# GBxCart_RW_v1_0_Schematic.net
KiCad netlist of a schematic drawn in EAGLE
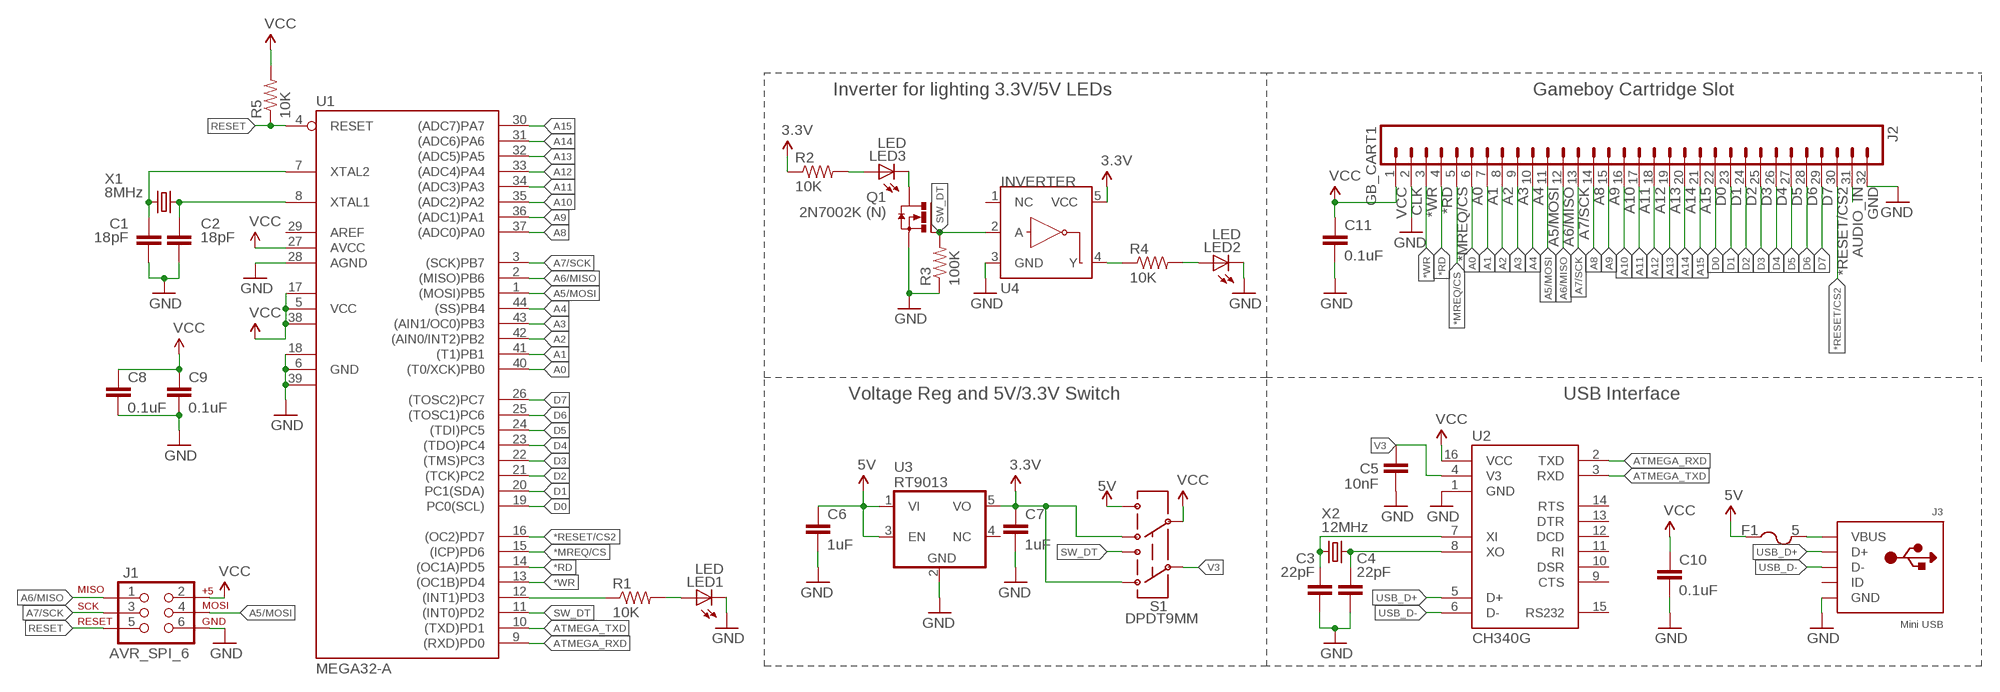
[diagram p0: schematic, sheet 1]

(export (version "E")
  (design (tool "Eeschema 10.0.6"))
  (components
    (comp (ref "C1")
      (value "18pF")
      (footprint "eagle-import:C0805K")
      (libsource (lib "eagle-import") (part "CAP0805"))
    )
    (comp (ref "C2")
      (value "18pF")
      (footprint "eagle-import:C0805K")
      (libsource (lib "eagle-import") (part "CAP0805"))
    )
    (comp (ref "C3")
      (value "22pF")
      (footprint "eagle-import:C0805K")
      (libsource (lib "eagle-import") (part "CAP0805"))
    )
    (comp (ref "C4")
      (value "22pF")
      (footprint "eagle-import:C0805K")
      (libsource (lib "eagle-import") (part "CAP0805"))
    )
    (comp (ref "C5")
      (value "10nF")
      (footprint "eagle-import:C0805K")
      (libsource (lib "eagle-import") (part "CAP0805"))
    )
    (comp (ref "C6")
      (value "1uF")
      (footprint "eagle-import:C0805K")
      (libsource (lib "eagle-import") (part "CAP0805"))
    )
    (comp (ref "C7")
      (value "1uF")
      (footprint "eagle-import:C0805K")
      (libsource (lib "eagle-import") (part "CAP0805"))
    )
    (comp (ref "C8")
      (value "0.1uF")
      (footprint "eagle-import:C0805K")
      (libsource (lib "eagle-import") (part "CAP0805"))
    )
    (comp (ref "C9")
      (value "0.1uF")
      (footprint "eagle-import:C0805K")
      (libsource (lib "eagle-import") (part "CAP0805"))
    )
    (comp (ref "C10")
      (value "0.1uF")
      (footprint "eagle-import:C0805K")
      (libsource (lib "eagle-import") (part "CAP0805"))
    )
    (comp (ref "C11")
      (value "0.1uF")
      (footprint "eagle-import:C0805K")
      (libsource (lib "eagle-import") (part "CAP0805"))
    )
    (comp (ref "F1")
      (value "5")
      (footprint "eagle-import:R1206")
      (libsource (lib "eagle-import") (part "PTCFUSE-1206"))
    )
    (comp (ref "J1")
      (value "AVR_SPI_6")
      (footprint "eagle-import:2X3_2")
      (libsource (lib "eagle-import") (part "AVR_SPI_PRG_6"))
    )
    (comp (ref "J2")
      (value "GB_CART1")
      (footprint "eagle-import:GB_CART_1")
      (libsource (lib "eagle-import") (part "GB_CART1"))
    )
    (comp (ref "J3")
      (value "Mini USB")
      (footprint "eagle-import:USB-MINIB")
      (libsource (lib "eagle-import") (part "USBMINIB"))
    )
    (comp (ref "LED1")
      (value "LED")
      (footprint "eagle-import:CHIP-LED0805")
      (libsource (lib "eagle-import") (part "LEDCHIP-LED0805"))
    )
    (comp (ref "LED2")
      (value "LED")
      (footprint "eagle-import:CHIP-LED0805")
      (libsource (lib "eagle-import") (part "LEDCHIP-LED0805"))
    )
    (comp (ref "LED3")
      (value "LED")
      (footprint "eagle-import:CHIP-LED0805")
      (libsource (lib "eagle-import") (part "LEDCHIP-LED0805"))
    )
    (comp (ref "Q1")
      (value "2N7002K (N)")
      (footprint "eagle-import:SOT-23")
      (libsource (lib "eagle-import") (part "2N7002K_(N)SOT-23"))
    )
    (comp (ref "R1")
      (value "10K")
      (footprint "eagle-import:R0805_2")
      (libsource (lib "eagle-import") (part "R-US_R0805_2"))
    )
    (comp (ref "R2")
      (value "10K")
      (footprint "eagle-import:R0805_2")
      (libsource (lib "eagle-import") (part "R-US_R0805_2"))
    )
    (comp (ref "R3")
      (value "100K")
      (footprint "eagle-import:R0805_2")
      (libsource (lib "eagle-import") (part "R-US_R0805_2"))
    )
    (comp (ref "R4")
      (value "10K")
      (footprint "eagle-import:R0805_2")
      (libsource (lib "eagle-import") (part "R-US_R0805_2"))
    )
    (comp (ref "R5")
      (value "10K")
      (footprint "eagle-import:R0805_2")
      (libsource (lib "eagle-import") (part "R-US_R0805_2"))
    )
    (comp (ref "S1")
      (value "DPDT9MM")
      (footprint "eagle-import:DPDT-3")
      (libsource (lib "eagle-import") (part "SWITCH-DPDT9MM-DIP"))
    )
    (comp (ref "U1")
      (value "MEGA32-A")
      (footprint "eagle-import:TQFP44")
      (libsource (lib "eagle-import") (part "MEGA32-A"))
    )
    (comp (ref "U2")
      (value "CH340G")
      (footprint "eagle-import:SO16")
      (libsource (lib "eagle-import") (part "CH340G"))
    )
    (comp (ref "U3")
      (value "RT9013")
      (footprint "eagle-import:SOT23-5L")
      (libsource (lib "eagle-import") (part "RT9013"))
    )
    (comp (ref "U4")
      (value "INVERTER")
      (footprint "eagle-import:SOT23-5")
      (libsource (lib "eagle-import") (part "INVERTER"))
    )
    (comp (ref "X1")
      (value "8MHz")
      (footprint "eagle-import:HC49U-V")
      (libsource (lib "eagle-import") (part "CRYSTALHC49U-V"))
    )
    (comp (ref "X2")
      (value "12MHz")
      (footprint "eagle-import:HC49U-V")
      (libsource (lib "eagle-import") (part "CRYSTALHC49U-V"))
    )
  )
  (nets
    (net (code "1") (name "*MREQ{slash}CS") (class "Default")
      (node (ref "J2") (pin "5") (pinfunction "5_5") (pintype "passive"))
      (node (ref "U1") (pin "15") (pinfunction "(ICP)PD6_15") (pintype "bidirectional"))
    )
    (net (code "2") (name "*RD") (class "Default")
      (node (ref "J2") (pin "4") (pinfunction "4_4") (pintype "passive"))
      (node (ref "U1") (pin "14") (pinfunction "(OC1A)PD5_14") (pintype "bidirectional"))
    )
    (net (code "3") (name "*RESET{slash}CS2") (class "Default")
      (node (ref "J2") (pin "30") (pinfunction "30_30") (pintype "passive"))
      (node (ref "U1") (pin "16") (pinfunction "(OC2)PD7_16") (pintype "bidirectional"))
    )
    (net (code "4") (name "*WR") (class "Default")
      (node (ref "J2") (pin "3") (pinfunction "3_3") (pintype "passive"))
      (node (ref "U1") (pin "13") (pinfunction "(OC1B)PD4_13") (pintype "bidirectional"))
    )
    (net (code "5") (name "/AREF") (class "Default")
      (node (ref "U1") (pin "29") (pinfunction "AREF_29") (pintype "power_in"))
    )
    (net (code "6") (name "/AUDIO_IN") (class "Default")
      (node (ref "J2") (pin "31") (pinfunction "31_31") (pintype "passive"))
    )
    (net (code "7") (name "3.3V") (class "Default")
      (node (ref "C7") (pin "1") (pinfunction "1_1") (pintype "passive"))
      (node (ref "R2") (pin "1") (pinfunction "1_1") (pintype "passive"))
      (node (ref "S1") (pin "1") (pinfunction "1_1") (pintype "bidirectional"))
      (node (ref "S1") (pin "4") (pinfunction "4_4") (pintype "bidirectional"))
      (node (ref "U3") (pin "5") (pinfunction "VO_5") (pintype "passive"))
      (node (ref "U4") (pin "5") (pinfunction "VCC_5") (pintype "bidirectional"))
    )
    (net (code "8") (name "5V") (class "Default")
      (node (ref "C6") (pin "1") (pinfunction "1_1") (pintype "passive"))
      (node (ref "F1") (pin "1") (pinfunction "1_1") (pintype "passive"))
      (node (ref "S1") (pin "6") (pinfunction "6_6") (pintype "bidirectional"))
      (node (ref "U3") (pin "1") (pinfunction "VI_1") (pintype "input"))
      (node (ref "U3") (pin "3") (pinfunction "EN_3") (pintype "input"))
    )
    (net (code "9") (name "A0") (class "Default")
      (node (ref "J2") (pin "6") (pinfunction "6_6") (pintype "passive"))
      (node (ref "U1") (pin "40") (pinfunction "(T0/XCK)PB0_40") (pintype "bidirectional"))
    )
    (net (code "10") (name "A1") (class "Default")
      (node (ref "J2") (pin "7") (pinfunction "7_7") (pintype "passive"))
      (node (ref "U1") (pin "41") (pinfunction "(T1)PB1_41") (pintype "bidirectional"))
    )
    (net (code "11") (name "A2") (class "Default")
      (node (ref "J2") (pin "8") (pinfunction "8_8") (pintype "passive"))
      (node (ref "U1") (pin "42") (pinfunction "(AIN0/INT2)PB2_42") (pintype "bidirectional"))
    )
    (net (code "12") (name "A3") (class "Default")
      (node (ref "J2") (pin "9") (pinfunction "9_9") (pintype "passive"))
      (node (ref "U1") (pin "43") (pinfunction "(AIN1/OC0)PB3_43") (pintype "bidirectional"))
    )
    (net (code "13") (name "A4") (class "Default")
      (node (ref "J2") (pin "10") (pinfunction "10_10") (pintype "passive"))
      (node (ref "U1") (pin "44") (pinfunction "(SS)PB4_44") (pintype "bidirectional"))
    )
    (net (code "14") (name "A5{slash}MOSI") (class "Default")
      (node (ref "J1") (pin "4") (pinfunction "4_4") (pintype "passive"))
      (node (ref "J2") (pin "11") (pinfunction "11_11") (pintype "passive"))
      (node (ref "U1") (pin "1") (pinfunction "(MOSI)PB5_1") (pintype "bidirectional"))
    )
    (net (code "15") (name "A6{slash}MISO") (class "Default")
      (node (ref "J1") (pin "1") (pinfunction "1_1") (pintype "passive"))
      (node (ref "J2") (pin "12") (pinfunction "12_12") (pintype "passive"))
      (node (ref "U1") (pin "2") (pinfunction "(MISO)PB6_2") (pintype "bidirectional"))
    )
    (net (code "16") (name "A7{slash}SCK") (class "Default")
      (node (ref "J1") (pin "3") (pinfunction "3_3") (pintype "passive"))
      (node (ref "J2") (pin "13") (pinfunction "13_13") (pintype "passive"))
      (node (ref "U1") (pin "3") (pinfunction "(SCK)PB7_3") (pintype "bidirectional"))
    )
    (net (code "17") (name "A8") (class "Default")
      (node (ref "J2") (pin "14") (pinfunction "14_14") (pintype "passive"))
      (node (ref "U1") (pin "37") (pinfunction "(ADC0)PA0_37") (pintype "bidirectional"))
    )
    (net (code "18") (name "A9") (class "Default")
      (node (ref "J2") (pin "15") (pinfunction "15_15") (pintype "passive"))
      (node (ref "U1") (pin "36") (pinfunction "(ADC1)PA1_36") (pintype "bidirectional"))
    )
    (net (code "19") (name "A10") (class "Default")
      (node (ref "J2") (pin "16") (pinfunction "16_16") (pintype "passive"))
      (node (ref "U1") (pin "35") (pinfunction "(ADC2)PA2_35") (pintype "bidirectional"))
    )
    (net (code "20") (name "A11") (class "Default")
      (node (ref "J2") (pin "17") (pinfunction "17_17") (pintype "passive"))
      (node (ref "U1") (pin "34") (pinfunction "(ADC3)PA3_34") (pintype "bidirectional"))
    )
    (net (code "21") (name "A12") (class "Default")
      (node (ref "J2") (pin "18") (pinfunction "18_18") (pintype "passive"))
      (node (ref "U1") (pin "33") (pinfunction "(ADC4)PA4_33") (pintype "bidirectional"))
    )
    (net (code "22") (name "A13") (class "Default")
      (node (ref "J2") (pin "19") (pinfunction "19_19") (pintype "passive"))
      (node (ref "U1") (pin "32") (pinfunction "(ADC5)PA5_32") (pintype "bidirectional"))
    )
    (net (code "23") (name "A14") (class "Default")
      (node (ref "J2") (pin "20") (pinfunction "20_20") (pintype "passive"))
      (node (ref "U1") (pin "31") (pinfunction "(ADC6)PA6_31") (pintype "bidirectional"))
    )
    (net (code "24") (name "A15") (class "Default")
      (node (ref "J2") (pin "21") (pinfunction "21_21") (pintype "passive"))
      (node (ref "U1") (pin "30") (pinfunction "(ADC7)PA7_30") (pintype "bidirectional"))
    )
    (net (code "25") (name "ATMEGA_RXD") (class "Default")
      (node (ref "U1") (pin "9") (pinfunction "(RXD)PD0_9") (pintype "bidirectional"))
      (node (ref "U2") (pin "2") (pinfunction "TXD_2") (pintype "bidirectional"))
    )
    (net (code "26") (name "ATMEGA_TXD") (class "Default")
      (node (ref "U1") (pin "10") (pinfunction "(TXD)PD1_10") (pintype "bidirectional"))
      (node (ref "U2") (pin "3") (pinfunction "RXD_3") (pintype "bidirectional"))
    )
    (net (code "27") (name "D0") (class "Default")
      (node (ref "J2") (pin "22") (pinfunction "22_22") (pintype "passive"))
      (node (ref "U1") (pin "19") (pinfunction "PC0(SCL)_19") (pintype "bidirectional"))
    )
    (net (code "28") (name "D1") (class "Default")
      (node (ref "J2") (pin "23") (pinfunction "23_23") (pintype "passive"))
      (node (ref "U1") (pin "20") (pinfunction "PC1(SDA)_20") (pintype "bidirectional"))
    )
    (net (code "29") (name "D2") (class "Default")
      (node (ref "J2") (pin "24") (pinfunction "24_24") (pintype "passive"))
      (node (ref "U1") (pin "21") (pinfunction "(TCK)PC2_21") (pintype "bidirectional"))
    )
    (net (code "30") (name "D3") (class "Default")
      (node (ref "J2") (pin "25") (pinfunction "25_25") (pintype "passive"))
      (node (ref "U1") (pin "22") (pinfunction "(TMS)PC3_22") (pintype "bidirectional"))
    )
    (net (code "31") (name "D4") (class "Default")
      (node (ref "J2") (pin "26") (pinfunction "26_26") (pintype "passive"))
      (node (ref "U1") (pin "23") (pinfunction "(TDO)PC4_23") (pintype "bidirectional"))
    )
    (net (code "32") (name "D5") (class "Default")
      (node (ref "J2") (pin "27") (pinfunction "27_27") (pintype "passive"))
      (node (ref "U1") (pin "24") (pinfunction "(TDI)PC5_24") (pintype "bidirectional"))
    )
    (net (code "33") (name "D6") (class "Default")
      (node (ref "J2") (pin "28") (pinfunction "28_28") (pintype "passive"))
      (node (ref "U1") (pin "25") (pinfunction "(TOSC1)PC6_25") (pintype "bidirectional"))
    )
    (net (code "34") (name "D7") (class "Default")
      (node (ref "J2") (pin "29") (pinfunction "29_29") (pintype "passive"))
      (node (ref "U1") (pin "26") (pinfunction "(TOSC2)PC7_26") (pintype "bidirectional"))
    )
    (net (code "35") (name "GND") (class "Default")
      (node (ref "C1") (pin "2") (pinfunction "2_2") (pintype "passive"))
      (node (ref "C10") (pin "2") (pinfunction "2_2") (pintype "passive"))
      (node (ref "C11") (pin "2") (pinfunction "2_2") (pintype "passive"))
      (node (ref "C2") (pin "2") (pinfunction "2_2") (pintype "passive"))
      (node (ref "C3") (pin "2") (pinfunction "2_2") (pintype "passive"))
      (node (ref "C4") (pin "2") (pinfunction "2_2") (pintype "passive"))
      (node (ref "C5") (pin "2") (pinfunction "2_2") (pintype "passive"))
      (node (ref "C6") (pin "2") (pinfunction "2_2") (pintype "passive"))
      (node (ref "C7") (pin "2") (pinfunction "2_2") (pintype "passive"))
      (node (ref "C8") (pin "2") (pinfunction "2_2") (pintype "passive"))
      (node (ref "C9") (pin "2") (pinfunction "2_2") (pintype "passive"))
      (node (ref "J1") (pin "6") (pinfunction "6_6") (pintype "passive"))
      (node (ref "J2") (pin "2") (pinfunction "2_2") (pintype "passive"))
      (node (ref "J2") (pin "32") (pinfunction "32_32") (pintype "passive"))
      (node (ref "J3") (pin "GND") (pinfunction "GND_GND") (pintype "power_in"))
      (node (ref "LED1") (pin "C") (pinfunction "C_C") (pintype "passive"))
      (node (ref "LED2") (pin "C") (pinfunction "C_C") (pintype "passive"))
      (node (ref "Q1") (pin "2") (pinfunction "S_2") (pintype "passive"))
      (node (ref "R3") (pin "1") (pinfunction "1_1") (pintype "passive"))
      (node (ref "U1") (pin "18") (pinfunction "GND1_18") (pintype "power_in"))
      (node (ref "U1") (pin "28") (pinfunction "AGND_28") (pintype "power_in"))
      (node (ref "U1") (pin "39") (pinfunction "GND2_39") (pintype "power_in"))
      (node (ref "U1") (pin "6") (pinfunction "GND_6") (pintype "power_in"))
      (node (ref "U2") (pin "1") (pinfunction "GND_1") (pintype "power_in"))
      (node (ref "U3") (pin "2") (pinfunction "GND_2") (pintype "passive"))
      (node (ref "U4") (pin "3") (pinfunction "GND_3") (pintype "bidirectional"))
    )
    (net (code "36") (name "Net-(F1-Pad2)") (class "Default")
      (node (ref "F1") (pin "2") (pinfunction "2_2") (pintype "passive"))
      (node (ref "J3") (pin "VBUS") (pinfunction "VBUS_VBUS") (pintype "power_in"))
    )
    (net (code "37") (name "Net-(LED1-PadA)") (class "Default")
      (node (ref "LED1") (pin "A") (pinfunction "A_A") (pintype "passive"))
      (node (ref "R1") (pin "2") (pinfunction "2_2") (pintype "passive"))
    )
    (net (code "38") (name "Net-(LED2-PadA)") (class "Default")
      (node (ref "LED2") (pin "A") (pinfunction "A_A") (pintype "passive"))
      (node (ref "R4") (pin "2") (pinfunction "2_2") (pintype "passive"))
    )
    (net (code "39") (name "Net-(LED3-PadA)") (class "Default")
      (node (ref "LED3") (pin "A") (pinfunction "A_A") (pintype "passive"))
      (node (ref "R2") (pin "2") (pinfunction "2_2") (pintype "passive"))
    )
    (net (code "40") (name "Net-(Q1-D)") (class "Default")
      (node (ref "LED3") (pin "C") (pinfunction "C_C") (pintype "passive"))
      (node (ref "Q1") (pin "3") (pinfunction "D_3") (pintype "passive"))
    )
    (net (code "41") (name "Net-(U1-(INT1)PD3)") (class "Default")
      (node (ref "R1") (pin "1") (pinfunction "1_1") (pintype "passive"))
      (node (ref "U1") (pin "12") (pinfunction "(INT1)PD3_12") (pintype "bidirectional"))
    )
    (net (code "42") (name "Net-(U1-XTAL1)") (class "Default")
      (node (ref "C2") (pin "1") (pinfunction "1_1") (pintype "passive"))
      (node (ref "U1") (pin "8") (pinfunction "XTAL1_8") (pintype "bidirectional"))
      (node (ref "X1") (pin "1") (pinfunction "1_1") (pintype "passive"))
    )
    (net (code "43") (name "Net-(U1-XTAL2)") (class "Default")
      (node (ref "C1") (pin "1") (pinfunction "1_1") (pintype "passive"))
      (node (ref "U1") (pin "7") (pinfunction "XTAL2_7") (pintype "bidirectional"))
      (node (ref "X1") (pin "2") (pinfunction "2_2") (pintype "passive"))
    )
    (net (code "44") (name "Net-(U2-XI)") (class "Default")
      (node (ref "C3") (pin "1") (pinfunction "1_1") (pintype "passive"))
      (node (ref "U2") (pin "7") (pinfunction "XI_7") (pintype "bidirectional"))
      (node (ref "X2") (pin "2") (pinfunction "2_2") (pintype "passive"))
    )
    (net (code "45") (name "Net-(U2-XO)") (class "Default")
      (node (ref "C4") (pin "1") (pinfunction "1_1") (pintype "passive"))
      (node (ref "U2") (pin "8") (pinfunction "XO_8") (pintype "bidirectional"))
      (node (ref "X2") (pin "1") (pinfunction "1_1") (pintype "passive"))
    )
    (net (code "46") (name "Net-(U4-Y)") (class "Default")
      (node (ref "R4") (pin "1") (pinfunction "1_1") (pintype "passive"))
      (node (ref "U4") (pin "4") (pinfunction "Y_4") (pintype "bidirectional"))
    )
    (net (code "47") (name "RESET") (class "Default")
      (node (ref "J1") (pin "5") (pinfunction "5_5") (pintype "passive"))
      (node (ref "R5") (pin "1") (pinfunction "1_1") (pintype "passive"))
      (node (ref "U1") (pin "4") (pinfunction "RESET_4") (pintype "input"))
    )
    (net (code "48") (name "SW_DT") (class "Default")
      (node (ref "Q1") (pin "1") (pinfunction "G_1") (pintype "passive"))
      (node (ref "R3") (pin "2") (pinfunction "2_2") (pintype "passive"))
      (node (ref "S1") (pin "3") (pinfunction "3_3") (pintype "bidirectional"))
      (node (ref "U1") (pin "11") (pinfunction "(INT0)PD2_11") (pintype "bidirectional"))
      (node (ref "U4") (pin "2") (pinfunction "A_2") (pintype "bidirectional"))
    )
    (net (code "49") (name "USB_D+") (class "Default")
      (node (ref "J3") (pin "D+") (pinfunction "D+_D+") (pintype "bidirectional"))
      (node (ref "U2") (pin "5") (pinfunction "D+_5") (pintype "bidirectional"))
    )
    (net (code "50") (name "USB_D-") (class "Default")
      (node (ref "J3") (pin "D-") (pinfunction "D-_D-") (pintype "bidirectional"))
      (node (ref "U2") (pin "6") (pinfunction "D-_6") (pintype "bidirectional"))
    )
    (net (code "51") (name "V3") (class "Default")
      (node (ref "C5") (pin "1") (pinfunction "1_1") (pintype "passive"))
      (node (ref "S1") (pin "2") (pinfunction "2_2") (pintype "bidirectional"))
      (node (ref "U2") (pin "4") (pinfunction "V3_4") (pintype "power_in"))
    )
    (net (code "52") (name "VCC") (class "Default")
      (node (ref "C10") (pin "1") (pinfunction "1_1") (pintype "passive"))
      (node (ref "C11") (pin "1") (pinfunction "1_1") (pintype "passive"))
      (node (ref "C8") (pin "1") (pinfunction "1_1") (pintype "passive"))
      (node (ref "C9") (pin "1") (pinfunction "1_1") (pintype "passive"))
      (node (ref "J1") (pin "2") (pinfunction "2_2") (pintype "passive"))
      (node (ref "J2") (pin "1") (pinfunction "1_1") (pintype "passive"))
      (node (ref "R5") (pin "2") (pinfunction "2_2") (pintype "passive"))
      (node (ref "S1") (pin "5") (pinfunction "5_5") (pintype "bidirectional"))
      (node (ref "U1") (pin "17") (pinfunction "VCC1_17") (pintype "power_in"))
      (node (ref "U1") (pin "27") (pinfunction "AVCC_27") (pintype "power_in"))
      (node (ref "U1") (pin "38") (pinfunction "VCC2_38") (pintype "power_in"))
      (node (ref "U1") (pin "5") (pinfunction "VCC_5") (pintype "power_in"))
      (node (ref "U2") (pin "16") (pinfunction "VCC_16") (pintype "power_in"))
    )
    (net (code "53") (name "unconnected-(J3-PadID)") (class "Default")
      (node (ref "J3") (pin "ID") (pinfunction "ID_ID") (pintype "bidirectional"))
    )
    (net (code "54") (name "unconnected-(U2-CTS-Pad9)") (class "Default")
      (node (ref "U2") (pin "9") (pinfunction "CTS_9") (pintype "bidirectional"))
    )
    (net (code "55") (name "unconnected-(U2-DCD-Pad12)") (class "Default")
      (node (ref "U2") (pin "12") (pinfunction "DCD_12") (pintype "bidirectional"))
    )
    (net (code "56") (name "unconnected-(U2-DSR-Pad10)") (class "Default")
      (node (ref "U2") (pin "10") (pinfunction "DSR_10") (pintype "bidirectional"))
    )
    (net (code "57") (name "unconnected-(U2-DTR-Pad13)") (class "Default")
      (node (ref "U2") (pin "13") (pinfunction "DTR_13") (pintype "bidirectional"))
    )
    (net (code "58") (name "unconnected-(U2-RI-Pad11)") (class "Default")
      (node (ref "U2") (pin "11") (pinfunction "RI_11") (pintype "bidirectional"))
    )
    (net (code "59") (name "unconnected-(U2-RS232-Pad15)") (class "Default")
      (node (ref "U2") (pin "15") (pinfunction "RS232_15") (pintype "bidirectional"))
    )
    (net (code "60") (name "unconnected-(U2-RTS-Pad14)") (class "Default")
      (node (ref "U2") (pin "14") (pinfunction "RTS_14") (pintype "bidirectional"))
    )
    (net (code "61") (name "unconnected-(U3-NC-Pad4)") (class "Default")
      (node (ref "U3") (pin "4") (pinfunction "NC_4") (pintype "no_connect"))
    )
    (net (code "62") (name "unconnected-(U4-NC-Pad1)") (class "Default")
      (node (ref "U4") (pin "1") (pinfunction "NC_1") (pintype "bidirectional"))
    )
  )
)
